# sub.net
KiCad netlist of a schematic drawn in EAGLE
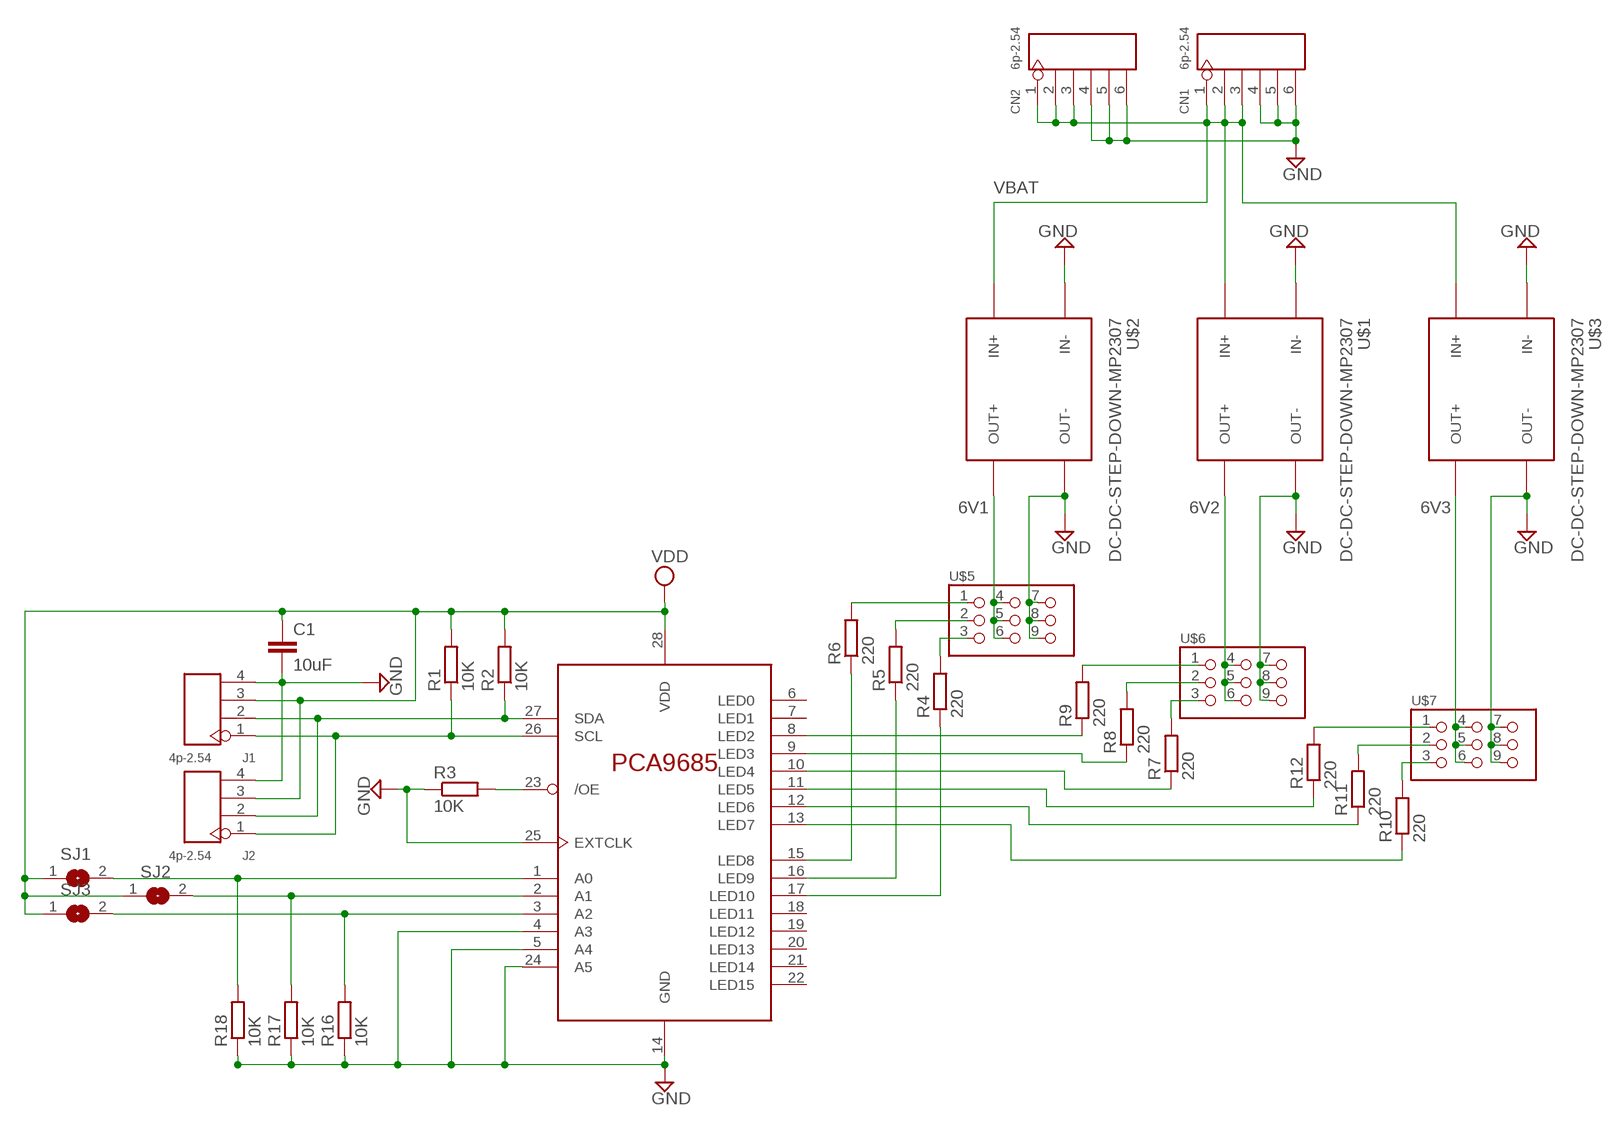
[diagram p0: schematic, sheet 1]

(export (version "E")
  (design (tool "Eeschema 10.0.6"))
  (components
    (comp (ref "C1")
      (value "10uF")
      (footprint "eagle-import:C0805")
      (libsource (lib "eagle-import") (part "C-EUC0805"))
    )
    (comp (ref "CN1")
      (value "6p-2.54")
      (footprint "eagle-import:H6-2.54")
      (fields (field (name "MPN") "F185-1106A1BSYC1"))
      (libsource (lib "eagle-import") (part "DIP-BLACK-FEMALE-HEADER-VERT(6P-2.54)"))
    )
    (comp (ref "CN2")
      (value "6p-2.54")
      (footprint "eagle-import:H6-2.54")
      (fields (field (name "MPN") "F185-1106A1BSYC1"))
      (libsource (lib "eagle-import") (part "DIP-BLACK-FEMALE-HEADER-VERT(6P-2.54)"))
    )
    (comp (ref "J1")
      (value "4p-2.54")
      (footprint "eagle-import:H4-2.54")
      (fields (field (name "MPN") "F185-1104A1BSYA1"))
      (libsource (lib "eagle-import") (part "DIP-BLACK-FEMALE-HEADER-VERT(4P-2.54)"))
    )
    (comp (ref "J2")
      (value "4p-2.54")
      (footprint "eagle-import:H4-2.54")
      (fields (field (name "MPN") "F185-1104A1BSYA1"))
      (libsource (lib "eagle-import") (part "DIP-BLACK-FEMALE-HEADER-VERT(4P-2.54)"))
    )
    (comp (ref "R1")
      (value "10K")
      (footprint "eagle-import:M0805")
      (libsource (lib "eagle-import") (part "R-EU_M0805"))
    )
    (comp (ref "R2")
      (value "10K")
      (footprint "eagle-import:M0805")
      (libsource (lib "eagle-import") (part "R-EU_M0805"))
    )
    (comp (ref "R3")
      (value "10K")
      (footprint "eagle-import:M0805")
      (libsource (lib "eagle-import") (part "R-EU_M0805"))
    )
    (comp (ref "R4")
      (value "220")
      (footprint "eagle-import:M0805")
      (libsource (lib "eagle-import") (part "R-EU_M0805"))
    )
    (comp (ref "R5")
      (value "220")
      (footprint "eagle-import:M0805")
      (libsource (lib "eagle-import") (part "R-EU_M0805"))
    )
    (comp (ref "R6")
      (value "220")
      (footprint "eagle-import:M0805")
      (libsource (lib "eagle-import") (part "R-EU_M0805"))
    )
    (comp (ref "R7")
      (value "220")
      (footprint "eagle-import:M0805")
      (libsource (lib "eagle-import") (part "R-EU_M0805"))
    )
    (comp (ref "R8")
      (value "220")
      (footprint "eagle-import:M0805")
      (libsource (lib "eagle-import") (part "R-EU_M0805"))
    )
    (comp (ref "R9")
      (value "220")
      (footprint "eagle-import:M0805")
      (libsource (lib "eagle-import") (part "R-EU_M0805"))
    )
    (comp (ref "R10")
      (value "220")
      (footprint "eagle-import:M0805")
      (libsource (lib "eagle-import") (part "R-EU_M0805"))
    )
    (comp (ref "R11")
      (value "220")
      (footprint "eagle-import:M0805")
      (libsource (lib "eagle-import") (part "R-EU_M0805"))
    )
    (comp (ref "R12")
      (value "220")
      (footprint "eagle-import:M0805")
      (libsource (lib "eagle-import") (part "R-EU_M0805"))
    )
    (comp (ref "R16")
      (value "10K")
      (footprint "eagle-import:M0805")
      (libsource (lib "eagle-import") (part "R-EU_M0805"))
    )
    (comp (ref "R17")
      (value "10K")
      (footprint "eagle-import:M0805")
      (libsource (lib "eagle-import") (part "R-EU_M0805"))
    )
    (comp (ref "R18")
      (value "10K")
      (footprint "eagle-import:M0805")
      (libsource (lib "eagle-import") (part "R-EU_M0805"))
    )
    (comp (ref "SJ1") (value "SJ") (footprint "eagle-import:SJ") (libsource (lib "eagle-import") (part "SJ")))
    (comp (ref "SJ2") (value "SJ") (footprint "eagle-import:SJ") (libsource (lib "eagle-import") (part "SJ")))
    (comp (ref "SJ3") (value "SJ") (footprint "eagle-import:SJ") (libsource (lib "eagle-import") (part "SJ")))
    (comp (ref "U$1")
      (value "DC-DC-STEP-DOWN-MP2307")
      (footprint "eagle-import:DC-DC-STEP-DOWN-MP2307")
      (libsource (lib "eagle-import") (part "DC-DC-STEP-DOWN-MP2307"))
    )
    (comp (ref "U$2")
      (value "DC-DC-STEP-DOWN-MP2307")
      (footprint "eagle-import:DC-DC-STEP-DOWN-MP2307")
      (libsource (lib "eagle-import") (part "DC-DC-STEP-DOWN-MP2307"))
    )
    (comp (ref "U$3")
      (value "DC-DC-STEP-DOWN-MP2307")
      (footprint "eagle-import:DC-DC-STEP-DOWN-MP2307")
      (libsource (lib "eagle-import") (part "DC-DC-STEP-DOWN-MP2307"))
    )
    (comp (ref "U$4")
      (value "PCA9685PW")
      (footprint "eagle-import:TSSOP28")
      (libsource (lib "eagle-import") (part "PCA9685PW"))
    )
    (comp (ref "U$5")
      (value "PIN_3X3")
      (footprint "eagle-import:PIN_3X3")
      (libsource (lib "eagle-import") (part "PIN_3X3"))
    )
    (comp (ref "U$6")
      (value "PIN_3X3")
      (footprint "eagle-import:PIN_3X3")
      (libsource (lib "eagle-import") (part "PIN_3X3"))
    )
    (comp (ref "U$7")
      (value "PIN_3X3")
      (footprint "eagle-import:PIN_3X3")
      (libsource (lib "eagle-import") (part "PIN_3X3"))
    )
  )
  (nets
    (net (code "1") (name "/6V1") (class "Default")
      (node (ref "U$2") (pin "OUT+") (pinfunction "OUT+_OUT+") (pintype "bidirectional"))
      (node (ref "U$5") (pin "4") (pinfunction "4_4") (pintype "bidirectional"))
      (node (ref "U$5") (pin "5") (pinfunction "5_5") (pintype "bidirectional"))
      (node (ref "U$5") (pin "6") (pinfunction "6_6") (pintype "bidirectional"))
    )
    (net (code "2") (name "/6V2") (class "Default")
      (node (ref "U$1") (pin "OUT+") (pinfunction "OUT+_OUT+") (pintype "bidirectional"))
      (node (ref "U$6") (pin "4") (pinfunction "4_4") (pintype "bidirectional"))
      (node (ref "U$6") (pin "5") (pinfunction "5_5") (pintype "bidirectional"))
      (node (ref "U$6") (pin "6") (pinfunction "6_6") (pintype "bidirectional"))
    )
    (net (code "3") (name "/6V3") (class "Default")
      (node (ref "U$3") (pin "OUT+") (pinfunction "OUT+_OUT+") (pintype "bidirectional"))
      (node (ref "U$7") (pin "4") (pinfunction "4_4") (pintype "bidirectional"))
      (node (ref "U$7") (pin "5") (pinfunction "5_5") (pintype "bidirectional"))
      (node (ref "U$7") (pin "6") (pinfunction "6_6") (pintype "bidirectional"))
    )
    (net (code "4") (name "/VBAT") (class "Default")
      (node (ref "CN1") (pin "1") (pinfunction "1_1") (pintype "bidirectional"))
      (node (ref "CN1") (pin "2") (pinfunction "2_2") (pintype "bidirectional"))
      (node (ref "CN1") (pin "3") (pinfunction "3_3") (pintype "bidirectional"))
      (node (ref "CN2") (pin "1") (pinfunction "1_1") (pintype "bidirectional"))
      (node (ref "CN2") (pin "2") (pinfunction "2_2") (pintype "bidirectional"))
      (node (ref "CN2") (pin "3") (pinfunction "3_3") (pintype "bidirectional"))
      (node (ref "U$1") (pin "IN+") (pinfunction "IN+_IN+") (pintype "bidirectional"))
      (node (ref "U$2") (pin "IN+") (pinfunction "IN+_IN+") (pintype "bidirectional"))
      (node (ref "U$3") (pin "IN+") (pinfunction "IN+_IN+") (pintype "bidirectional"))
    )
    (net (code "5") (name "GND") (class "Default")
      (node (ref "C1") (pin "2") (pinfunction "2_2") (pintype "passive"))
      (node (ref "CN1") (pin "4") (pinfunction "4_4") (pintype "bidirectional"))
      (node (ref "CN1") (pin "5") (pinfunction "5_5") (pintype "bidirectional"))
      (node (ref "CN1") (pin "6") (pinfunction "6_6") (pintype "bidirectional"))
      (node (ref "CN2") (pin "4") (pinfunction "4_4") (pintype "bidirectional"))
      (node (ref "CN2") (pin "5") (pinfunction "5_5") (pintype "bidirectional"))
      (node (ref "CN2") (pin "6") (pinfunction "6_6") (pintype "bidirectional"))
      (node (ref "J1") (pin "4") (pinfunction "P$4_4") (pintype "bidirectional"))
      (node (ref "J2") (pin "4") (pinfunction "P$4_4") (pintype "bidirectional"))
      (node (ref "R16") (pin "1") (pinfunction "1_1") (pintype "passive"))
      (node (ref "R17") (pin "1") (pinfunction "1_1") (pintype "passive"))
      (node (ref "R18") (pin "1") (pinfunction "1_1") (pintype "passive"))
      (node (ref "R3") (pin "1") (pinfunction "1_1") (pintype "passive"))
      (node (ref "U$1") (pin "IN-") (pinfunction "IN-_IN-") (pintype "bidirectional"))
      (node (ref "U$1") (pin "OUT-") (pinfunction "OUT-_OUT-") (pintype "bidirectional"))
      (node (ref "U$2") (pin "IN-") (pinfunction "IN-_IN-") (pintype "bidirectional"))
      (node (ref "U$2") (pin "OUT-") (pinfunction "OUT-_OUT-") (pintype "bidirectional"))
      (node (ref "U$3") (pin "IN-") (pinfunction "IN-_IN-") (pintype "bidirectional"))
      (node (ref "U$3") (pin "OUT-") (pinfunction "OUT-_OUT-") (pintype "bidirectional"))
      (node (ref "U$4") (pin "14") (pinfunction "GND_14") (pintype "power_in"))
      (node (ref "U$4") (pin "24") (pinfunction "A5_24") (pintype "bidirectional"))
      (node (ref "U$4") (pin "25") (pinfunction "EXTCLK_25") (pintype "input"))
      (node (ref "U$4") (pin "4") (pinfunction "A3_4") (pintype "bidirectional"))
      (node (ref "U$4") (pin "5") (pinfunction "A4_5") (pintype "bidirectional"))
      (node (ref "U$5") (pin "7") (pinfunction "7_7") (pintype "bidirectional"))
      (node (ref "U$5") (pin "8") (pinfunction "8_8") (pintype "bidirectional"))
      (node (ref "U$5") (pin "9") (pinfunction "9_9") (pintype "bidirectional"))
      (node (ref "U$6") (pin "7") (pinfunction "7_7") (pintype "bidirectional"))
      (node (ref "U$6") (pin "8") (pinfunction "8_8") (pintype "bidirectional"))
      (node (ref "U$6") (pin "9") (pinfunction "9_9") (pintype "bidirectional"))
      (node (ref "U$7") (pin "7") (pinfunction "7_7") (pintype "bidirectional"))
      (node (ref "U$7") (pin "8") (pinfunction "8_8") (pintype "bidirectional"))
      (node (ref "U$7") (pin "9") (pinfunction "9_9") (pintype "bidirectional"))
    )
    (net (code "6") (name "Net-(J1-P$1)") (class "Default")
      (node (ref "J1") (pin "1") (pinfunction "P$1_1") (pintype "bidirectional"))
      (node (ref "J2") (pin "1") (pinfunction "P$1_1") (pintype "bidirectional"))
      (node (ref "R1") (pin "1") (pinfunction "1_1") (pintype "passive"))
      (node (ref "U$4") (pin "26") (pinfunction "SCL_26") (pintype "bidirectional"))
    )
    (net (code "7") (name "Net-(J1-P$2)") (class "Default")
      (node (ref "J1") (pin "2") (pinfunction "P$2_2") (pintype "bidirectional"))
      (node (ref "J2") (pin "2") (pinfunction "P$2_2") (pintype "bidirectional"))
      (node (ref "R2") (pin "1") (pinfunction "1_1") (pintype "passive"))
      (node (ref "U$4") (pin "27") (pinfunction "SDA_27") (pintype "bidirectional"))
    )
    (net (code "8") (name "Net-(R4-Pad2)") (class "Default")
      (node (ref "R4") (pin "2") (pinfunction "2_2") (pintype "passive"))
      (node (ref "U$5") (pin "3") (pinfunction "3_3") (pintype "bidirectional"))
    )
    (net (code "9") (name "Net-(R5-Pad2)") (class "Default")
      (node (ref "R5") (pin "2") (pinfunction "2_2") (pintype "passive"))
      (node (ref "U$5") (pin "2") (pinfunction "2_2") (pintype "bidirectional"))
    )
    (net (code "10") (name "Net-(R6-Pad2)") (class "Default")
      (node (ref "R6") (pin "2") (pinfunction "2_2") (pintype "passive"))
      (node (ref "U$5") (pin "1") (pinfunction "1_1") (pintype "bidirectional"))
    )
    (net (code "11") (name "Net-(R7-Pad2)") (class "Default")
      (node (ref "R7") (pin "2") (pinfunction "2_2") (pintype "passive"))
      (node (ref "U$6") (pin "3") (pinfunction "3_3") (pintype "bidirectional"))
    )
    (net (code "12") (name "Net-(R8-Pad2)") (class "Default")
      (node (ref "R8") (pin "2") (pinfunction "2_2") (pintype "passive"))
      (node (ref "U$6") (pin "2") (pinfunction "2_2") (pintype "bidirectional"))
    )
    (net (code "13") (name "Net-(R9-Pad2)") (class "Default")
      (node (ref "R9") (pin "2") (pinfunction "2_2") (pintype "passive"))
      (node (ref "U$6") (pin "1") (pinfunction "1_1") (pintype "bidirectional"))
    )
    (net (code "14") (name "Net-(R10-Pad2)") (class "Default")
      (node (ref "R10") (pin "2") (pinfunction "2_2") (pintype "passive"))
      (node (ref "U$7") (pin "3") (pinfunction "3_3") (pintype "bidirectional"))
    )
    (net (code "15") (name "Net-(R11-Pad2)") (class "Default")
      (node (ref "R11") (pin "2") (pinfunction "2_2") (pintype "passive"))
      (node (ref "U$7") (pin "2") (pinfunction "2_2") (pintype "bidirectional"))
    )
    (net (code "16") (name "Net-(R12-Pad2)") (class "Default")
      (node (ref "R12") (pin "2") (pinfunction "2_2") (pintype "passive"))
      (node (ref "U$7") (pin "1") (pinfunction "1_1") (pintype "bidirectional"))
    )
    (net (code "17") (name "Net-(U$4-A0)") (class "Default")
      (node (ref "R18") (pin "2") (pinfunction "2_2") (pintype "passive"))
      (node (ref "SJ1") (pin "2") (pinfunction "2_2") (pintype "passive"))
      (node (ref "U$4") (pin "1") (pinfunction "A0_1") (pintype "bidirectional"))
    )
    (net (code "18") (name "Net-(U$4-A1)") (class "Default")
      (node (ref "R17") (pin "2") (pinfunction "2_2") (pintype "passive"))
      (node (ref "SJ2") (pin "2") (pinfunction "2_2") (pintype "passive"))
      (node (ref "U$4") (pin "2") (pinfunction "A1_2") (pintype "bidirectional"))
    )
    (net (code "19") (name "Net-(U$4-A2)") (class "Default")
      (node (ref "R16") (pin "2") (pinfunction "2_2") (pintype "passive"))
      (node (ref "SJ3") (pin "2") (pinfunction "2_2") (pintype "passive"))
      (node (ref "U$4") (pin "3") (pinfunction "A2_3") (pintype "bidirectional"))
    )
    (net (code "20") (name "Net-(U$4-LED2)") (class "Default")
      (node (ref "R9") (pin "1") (pinfunction "1_1") (pintype "passive"))
      (node (ref "U$4") (pin "8") (pinfunction "LED2_8") (pintype "bidirectional"))
    )
    (net (code "21") (name "Net-(U$4-LED3)") (class "Default")
      (node (ref "R8") (pin "1") (pinfunction "1_1") (pintype "passive"))
      (node (ref "U$4") (pin "9") (pinfunction "LED3_9") (pintype "bidirectional"))
    )
    (net (code "22") (name "Net-(U$4-LED4)") (class "Default")
      (node (ref "R7") (pin "1") (pinfunction "1_1") (pintype "passive"))
      (node (ref "U$4") (pin "10") (pinfunction "LED4_10") (pintype "bidirectional"))
    )
    (net (code "23") (name "Net-(U$4-LED5)") (class "Default")
      (node (ref "R12") (pin "1") (pinfunction "1_1") (pintype "passive"))
      (node (ref "U$4") (pin "11") (pinfunction "LED5_11") (pintype "bidirectional"))
    )
    (net (code "24") (name "Net-(U$4-LED6)") (class "Default")
      (node (ref "R11") (pin "1") (pinfunction "1_1") (pintype "passive"))
      (node (ref "U$4") (pin "12") (pinfunction "LED6_12") (pintype "bidirectional"))
    )
    (net (code "25") (name "Net-(U$4-LED7)") (class "Default")
      (node (ref "R10") (pin "1") (pinfunction "1_1") (pintype "passive"))
      (node (ref "U$4") (pin "13") (pinfunction "LED7_13") (pintype "bidirectional"))
    )
    (net (code "26") (name "Net-(U$4-LED8)") (class "Default")
      (node (ref "R6") (pin "1") (pinfunction "1_1") (pintype "passive"))
      (node (ref "U$4") (pin "15") (pinfunction "LED8_15") (pintype "bidirectional"))
    )
    (net (code "27") (name "Net-(U$4-LED9)") (class "Default")
      (node (ref "R5") (pin "1") (pinfunction "1_1") (pintype "passive"))
      (node (ref "U$4") (pin "16") (pinfunction "LED9_16") (pintype "bidirectional"))
    )
    (net (code "28") (name "Net-(U$4-LED10)") (class "Default")
      (node (ref "R4") (pin "1") (pinfunction "1_1") (pintype "passive"))
      (node (ref "U$4") (pin "17") (pinfunction "LED10_17") (pintype "bidirectional"))
    )
    (net (code "29") (name "Net-(U$4-{slash}OE)") (class "Default")
      (node (ref "R3") (pin "2") (pinfunction "2_2") (pintype "passive"))
      (node (ref "U$4") (pin "23") (pinfunction "/OE_23") (pintype "bidirectional"))
    )
    (net (code "30") (name "VDD") (class "Default")
      (node (ref "C1") (pin "1") (pinfunction "1_1") (pintype "passive"))
      (node (ref "J1") (pin "3") (pinfunction "P$3_3") (pintype "bidirectional"))
      (node (ref "J2") (pin "3") (pinfunction "P$3_3") (pintype "bidirectional"))
      (node (ref "R1") (pin "2") (pinfunction "2_2") (pintype "passive"))
      (node (ref "R2") (pin "2") (pinfunction "2_2") (pintype "passive"))
      (node (ref "SJ1") (pin "1") (pinfunction "1_1") (pintype "passive"))
      (node (ref "SJ2") (pin "1") (pinfunction "1_1") (pintype "passive"))
      (node (ref "SJ3") (pin "1") (pinfunction "1_1") (pintype "passive"))
      (node (ref "U$4") (pin "28") (pinfunction "VDD_28") (pintype "power_in"))
    )
    (net (code "31") (name "unconnected-(U$4-LED0-Pad6)") (class "Default")
      (node (ref "U$4") (pin "6") (pinfunction "LED0_6") (pintype "bidirectional"))
    )
    (net (code "32") (name "unconnected-(U$4-LED1-Pad7)") (class "Default")
      (node (ref "U$4") (pin "7") (pinfunction "LED1_7") (pintype "bidirectional"))
    )
    (net (code "33") (name "unconnected-(U$4-LED11-Pad18)") (class "Default")
      (node (ref "U$4") (pin "18") (pinfunction "LED11_18") (pintype "bidirectional"))
    )
    (net (code "34") (name "unconnected-(U$4-LED12-Pad19)") (class "Default")
      (node (ref "U$4") (pin "19") (pinfunction "LED12_19") (pintype "bidirectional"))
    )
    (net (code "35") (name "unconnected-(U$4-LED13-Pad20)") (class "Default")
      (node (ref "U$4") (pin "20") (pinfunction "LED13_20") (pintype "bidirectional"))
    )
    (net (code "36") (name "unconnected-(U$4-LED14-Pad21)") (class "Default")
      (node (ref "U$4") (pin "21") (pinfunction "LED14_21") (pintype "bidirectional"))
    )
    (net (code "37") (name "unconnected-(U$4-LED15-Pad22)") (class "Default")
      (node (ref "U$4") (pin "22") (pinfunction "LED15_22") (pintype "bidirectional"))
    )
  )
)
